# MotorDrivers.net
KiCad netlist of a schematic drawn in Altium Designer
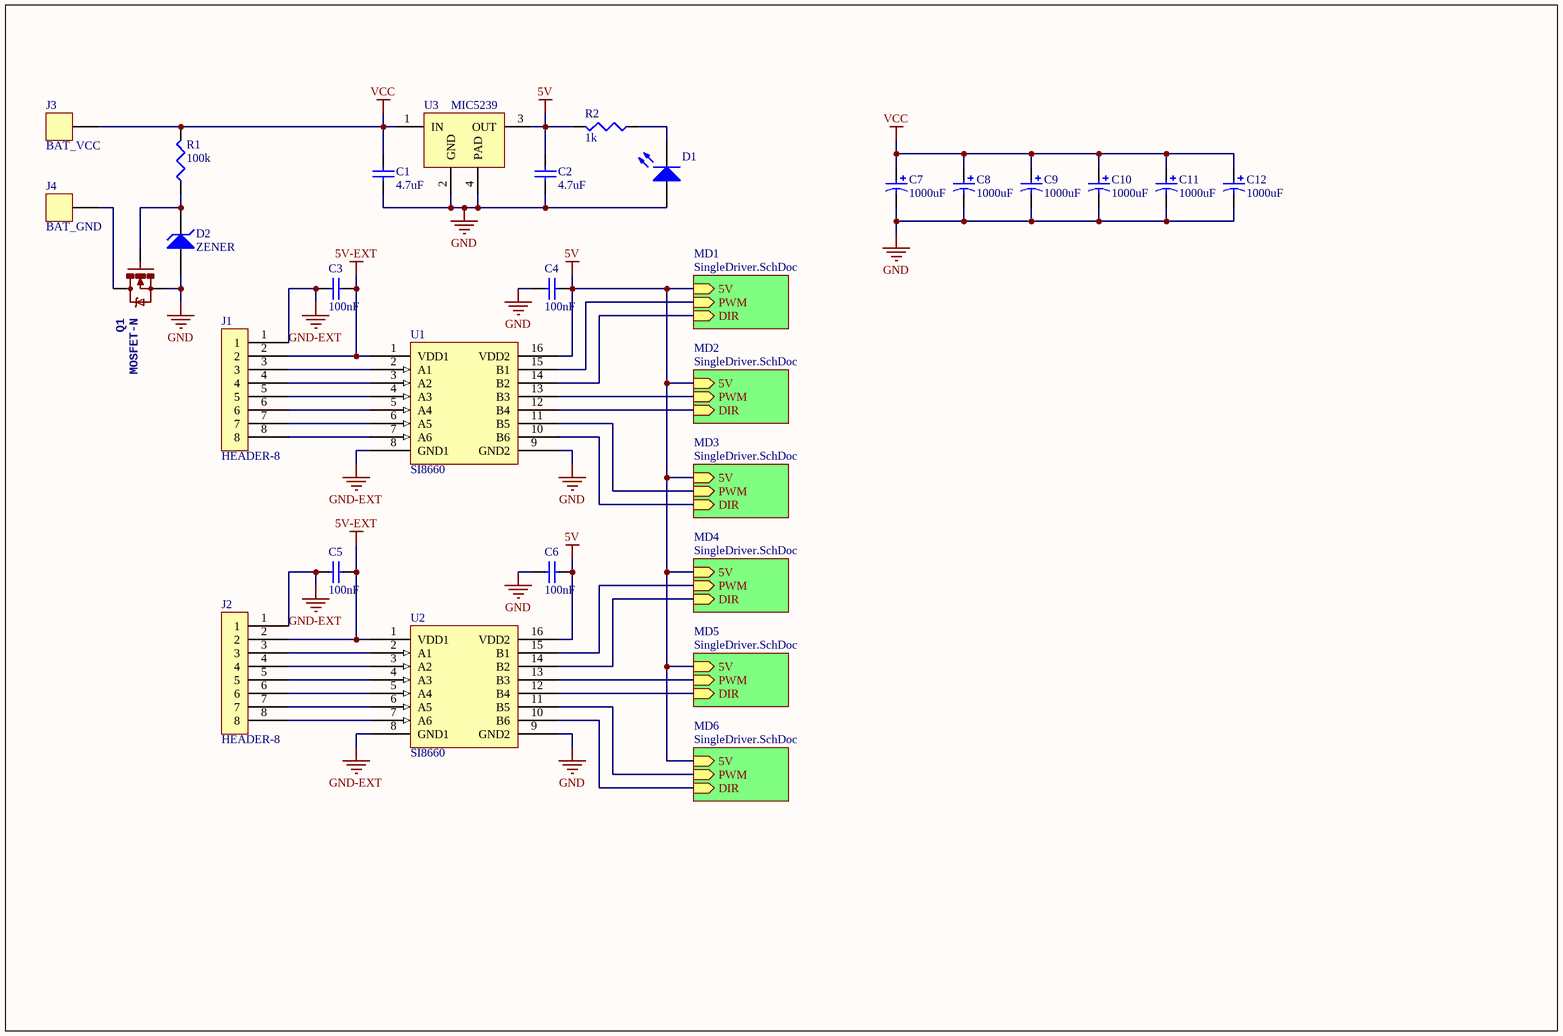
[diagram p0: MotorDrivers.SchDoc]

(export (version "E")
  (design (tool "Eeschema 10.0.6"))
  (components
    (comp (ref "C1")
      (value "4.7uF")
      (footprint "C1206")
      (description "Capacitor (Semiconductor SIM Model)")
      (fields (field (name "PUBLISHER") "Altium Limited"))
      (libsource (lib "Miscellaneous Devices") (part "Cap Semi"))
    )
    (comp (ref "C2")
      (value "4.7uF")
      (footprint "C1206")
      (description "Capacitor (Semiconductor SIM Model)")
      (fields (field (name "PUBLISHER") "Altium Limited"))
      (libsource (lib "Miscellaneous Devices") (part "Cap Semi"))
    )
    (comp (ref "C3")
      (value "100nF")
      (footprint "1608[0603]")
      (description "Capacitor (Semiconductor SIM Model)")
      (fields (field (name "PUBLISHER") "Altium Limited"))
      (libsource (lib "Miscellaneous Devices") (part "Cap Semi"))
    )
    (comp (ref "C4")
      (value "100nF")
      (footprint "1608[0603]")
      (description "Capacitor (Semiconductor SIM Model)")
      (fields (field (name "PUBLISHER") "Altium Limited"))
      (libsource (lib "Miscellaneous Devices") (part "Cap Semi"))
    )
    (comp (ref "C5")
      (value "100nF")
      (footprint "1608[0603]")
      (description "Capacitor (Semiconductor SIM Model)")
      (fields (field (name "PUBLISHER") "Altium Limited"))
      (libsource (lib "Miscellaneous Devices") (part "Cap Semi"))
    )
    (comp (ref "C6")
      (value "100nF")
      (footprint "1608[0603]")
      (description "Capacitor (Semiconductor SIM Model)")
      (fields (field (name "PUBLISHER") "Altium Limited"))
      (libsource (lib "Miscellaneous Devices") (part "Cap Semi"))
    )
    (comp (ref "C7")
      (value "1000uF")
      (footprint "cap_radial_20")
      (libsource (lib "passive") (part "cap_pol"))
    )
    (comp (ref "C8")
      (value "1000uF")
      (footprint "cap_radial_20")
      (libsource (lib "passive") (part "cap_pol"))
    )
    (comp (ref "C9")
      (value "1000uF")
      (footprint "cap_radial_20")
      (libsource (lib "passive") (part "cap_pol"))
    )
    (comp (ref "C10")
      (value "1000uF")
      (footprint "cap_radial_20")
      (libsource (lib "passive") (part "cap_pol"))
    )
    (comp (ref "C11")
      (value "1000uF")
      (footprint "cap_radial_20")
      (libsource (lib "passive") (part "cap_pol"))
    )
    (comp (ref "C12")
      (value "1000uF")
      (footprint "cap_radial_20")
      (libsource (lib "passive") (part "cap_pol"))
    )
    (comp (ref "D1")
      (value "LED2")
      (footprint "1608[0603]")
      (description "Typical RED, GREEN, YELLOW, AMBER GaAs LED")
      (fields (field (name "PUBLISHER") "Altium Limited"))
      (libsource (lib "Miscellaneous Devices") (part "LED2"))
    )
    (comp (ref "D2")
      (value "ZENER")
      (footprint "SODFL370X135-2N")
      (libsource (lib "power") (part "ZENER-DIODE"))
    )
    (comp (ref "J1")
      (value "HEADER-8")
      (footprint "MICRO-MATCH-8")
      (libsource (lib "connectors") (part "HEADER-8"))
    )
    (comp (ref "J2")
      (value "HEADER-8")
      (footprint "MICRO-MATCH-8")
      (libsource (lib "connectors") (part "HEADER-8"))
    )
    (comp (ref "J3")
      (value "BAT_VCC")
      (footprint "HIGH-POWER-VIA")
      (libsource (lib "connectors") (part "HEADER-1"))
    )
    (comp (ref "J4")
      (value "BAT_GND")
      (footprint "HIGH-POWER-VIA")
      (libsource (lib "connectors") (part "HEADER-1"))
    )
    (comp (ref "Q1") (value "MOSFET-N") (footprint "SOT669") (libsource (lib "mosfets") (part "MOSFET-N")))
    (comp (ref "R1")
      (value "100k")
      (footprint "J1-0603")
      (description "Resistor")
      (fields (field (name "PUBLISHER") "Altium Limited"))
      (libsource (lib "Miscellaneous Devices") (part "Res3"))
    )
    (comp (ref "R2")
      (value "1k")
      (footprint "J1-0603")
      (description "Resistor")
      (fields (field (name "PUBLISHER") "Altium Limited"))
      (libsource (lib "Miscellaneous Devices") (part "Res3"))
    )
    (comp (ref "U1") (value "SI8660") (footprint "SOIC16") (libsource (lib "digital") (part "SI8660")))
    (comp (ref "U2") (value "SI8660") (footprint "SOIC16") (libsource (lib "digital") (part "SI8660")))
    (comp (ref "U3")
      (value "MIC5239")
      (footprint "SOT230P700X180-4N")
      (libsource (lib "power") (part "MIC5239"))
    )
  )
  (nets
    (net (code "1") (name "/DIR") (class "Default")
      (node (ref "U2") (pin "10") (pinfunction "B6_10") (pintype "passive"))
    )
    (net (code "2") (name "/DIR_1") (class "Default")
      (node (ref "U1") (pin "14") (pinfunction "B2_14") (pintype "passive"))
    )
    (net (code "3") (name "/DIR_2") (class "Default")
      (node (ref "U1") (pin "12") (pinfunction "B4_12") (pintype "passive"))
    )
    (net (code "4") (name "/DIR_3") (class "Default")
      (node (ref "U1") (pin "10") (pinfunction "B6_10") (pintype "passive"))
    )
    (net (code "5") (name "/DIR_4") (class "Default")
      (node (ref "U2") (pin "14") (pinfunction "B2_14") (pintype "passive"))
    )
    (net (code "6") (name "/DIR_5") (class "Default")
      (node (ref "U2") (pin "12") (pinfunction "B4_12") (pintype "passive"))
    )
    (net (code "7") (name "/PWM") (class "Default")
      (node (ref "U2") (pin "11") (pinfunction "B5_11") (pintype "passive"))
    )
    (net (code "8") (name "/PWM_1") (class "Default")
      (node (ref "U1") (pin "15") (pinfunction "B1_15") (pintype "passive"))
    )
    (net (code "9") (name "/PWM_2") (class "Default")
      (node (ref "U1") (pin "13") (pinfunction "B3_13") (pintype "passive"))
    )
    (net (code "10") (name "/PWM_3") (class "Default")
      (node (ref "U1") (pin "11") (pinfunction "B5_11") (pintype "passive"))
    )
    (net (code "11") (name "/PWM_4") (class "Default")
      (node (ref "U2") (pin "15") (pinfunction "B1_15") (pintype "passive"))
    )
    (net (code "12") (name "/PWM_5") (class "Default")
      (node (ref "U2") (pin "13") (pinfunction "B3_13") (pintype "passive"))
    )
    (net (code "13") (name "5V") (class "Default")
      (node (ref "C2") (pin "2") (pinfunction "2_2") (pintype "passive"))
      (node (ref "C4") (pin "1") (pinfunction "1_1") (pintype "passive"))
      (node (ref "C6") (pin "1") (pinfunction "1_1") (pintype "passive"))
      (node (ref "R2") (pin "2") (pinfunction "2_2") (pintype "passive"))
      (node (ref "U1") (pin "16") (pinfunction "VDD2_16") (pintype "power_in"))
      (node (ref "U2") (pin "16") (pinfunction "VDD2_16") (pintype "power_in"))
      (node (ref "U3") (pin "3") (pinfunction "OUT_3") (pintype "power_in"))
    )
    (net (code "14") (name "5V-EXT") (class "Default")
      (node (ref "C3") (pin "1") (pinfunction "1_1") (pintype "passive"))
      (node (ref "C5") (pin "1") (pinfunction "1_1") (pintype "passive"))
      (node (ref "J1") (pin "2") (pinfunction "2_2") (pintype "passive"))
      (node (ref "J2") (pin "2") (pinfunction "2_2") (pintype "passive"))
      (node (ref "U1") (pin "1") (pinfunction "VDD1_1") (pintype "power_in"))
      (node (ref "U2") (pin "1") (pinfunction "VDD1_1") (pintype "power_in"))
    )
    (net (code "15") (name "GND") (class "Default")
      (node (ref "C1") (pin "1") (pinfunction "1_1") (pintype "passive"))
      (node (ref "C10") (pin "1") (pinfunction "1_1") (pintype "passive"))
      (node (ref "C11") (pin "1") (pinfunction "1_1") (pintype "passive"))
      (node (ref "C12") (pin "1") (pinfunction "1_1") (pintype "passive"))
      (node (ref "C2") (pin "1") (pinfunction "1_1") (pintype "passive"))
      (node (ref "C4") (pin "2") (pinfunction "2_2") (pintype "passive"))
      (node (ref "C6") (pin "2") (pinfunction "2_2") (pintype "passive"))
      (node (ref "C7") (pin "1") (pinfunction "1_1") (pintype "passive"))
      (node (ref "C8") (pin "1") (pinfunction "1_1") (pintype "passive"))
      (node (ref "C9") (pin "1") (pinfunction "1_1") (pintype "passive"))
      (node (ref "D1") (pin "1") (pinfunction "A_1") (pintype "passive"))
      (node (ref "D2") (pin "2") (pinfunction "2_2") (pintype "passive"))
      (node (ref "Q1") (pin "S") (pinfunction "S_S") (pintype "passive"))
      (node (ref "U1") (pin "9") (pinfunction "GND2_9") (pintype "power_in"))
      (node (ref "U2") (pin "9") (pinfunction "GND2_9") (pintype "power_in"))
      (node (ref "U3") (pin "2") (pinfunction "GND_2") (pintype "power_in"))
      (node (ref "U3") (pin "4") (pinfunction "PAD_4") (pintype "power_in"))
    )
    (net (code "16") (name "GND-EXT") (class "Default")
      (node (ref "C3") (pin "2") (pinfunction "2_2") (pintype "passive"))
      (node (ref "C5") (pin "2") (pinfunction "2_2") (pintype "passive"))
      (node (ref "J1") (pin "1") (pinfunction "1_1") (pintype "passive"))
      (node (ref "J2") (pin "1") (pinfunction "1_1") (pintype "passive"))
      (node (ref "U1") (pin "8") (pinfunction "GND1_8") (pintype "power_in"))
      (node (ref "U2") (pin "8") (pinfunction "GND1_8") (pintype "power_in"))
    )
    (net (code "17") (name "Net-(D1-K)") (class "Default")
      (node (ref "D1") (pin "2") (pinfunction "K_2") (pintype "passive"))
      (node (ref "R2") (pin "1") (pinfunction "1_1") (pintype "passive"))
    )
    (net (code "18") (name "Net-(D2-Pad1)") (class "Default")
      (node (ref "D2") (pin "1") (pinfunction "1_1") (pintype "passive"))
      (node (ref "Q1") (pin "G") (pinfunction "G_G") (pintype "passive"))
      (node (ref "R1") (pin "1") (pinfunction "1_1") (pintype "passive"))
    )
    (net (code "19") (name "Net-(J4-Pad1)") (class "Default")
      (node (ref "J4") (pin "1") (pinfunction "1_1") (pintype "passive"))
      (node (ref "Q1") (pin "D") (pinfunction "D_D") (pintype "passive"))
    )
    (net (code "20") (name "Net-(U1-A1)") (class "Default")
      (node (ref "J1") (pin "3") (pinfunction "3_3") (pintype "passive"))
      (node (ref "U1") (pin "2") (pinfunction "A1_2") (pintype "input"))
    )
    (net (code "21") (name "Net-(U1-A2)") (class "Default")
      (node (ref "J1") (pin "4") (pinfunction "4_4") (pintype "passive"))
      (node (ref "U1") (pin "3") (pinfunction "A2_3") (pintype "input"))
    )
    (net (code "22") (name "Net-(U1-A3)") (class "Default")
      (node (ref "J1") (pin "5") (pinfunction "5_5") (pintype "passive"))
      (node (ref "U1") (pin "4") (pinfunction "A3_4") (pintype "input"))
    )
    (net (code "23") (name "Net-(U1-A4)") (class "Default")
      (node (ref "J1") (pin "6") (pinfunction "6_6") (pintype "passive"))
      (node (ref "U1") (pin "5") (pinfunction "A4_5") (pintype "input"))
    )
    (net (code "24") (name "Net-(U1-A5)") (class "Default")
      (node (ref "J1") (pin "7") (pinfunction "7_7") (pintype "passive"))
      (node (ref "U1") (pin "6") (pinfunction "A5_6") (pintype "input"))
    )
    (net (code "25") (name "Net-(U1-A6)") (class "Default")
      (node (ref "J1") (pin "8") (pinfunction "8_8") (pintype "passive"))
      (node (ref "U1") (pin "7") (pinfunction "A6_7") (pintype "input"))
    )
    (net (code "26") (name "Net-(U2-A1)") (class "Default")
      (node (ref "J2") (pin "3") (pinfunction "3_3") (pintype "passive"))
      (node (ref "U2") (pin "2") (pinfunction "A1_2") (pintype "input"))
    )
    (net (code "27") (name "Net-(U2-A2)") (class "Default")
      (node (ref "J2") (pin "4") (pinfunction "4_4") (pintype "passive"))
      (node (ref "U2") (pin "3") (pinfunction "A2_3") (pintype "input"))
    )
    (net (code "28") (name "Net-(U2-A3)") (class "Default")
      (node (ref "J2") (pin "5") (pinfunction "5_5") (pintype "passive"))
      (node (ref "U2") (pin "4") (pinfunction "A3_4") (pintype "input"))
    )
    (net (code "29") (name "Net-(U2-A4)") (class "Default")
      (node (ref "J2") (pin "6") (pinfunction "6_6") (pintype "passive"))
      (node (ref "U2") (pin "5") (pinfunction "A4_5") (pintype "input"))
    )
    (net (code "30") (name "Net-(U2-A5)") (class "Default")
      (node (ref "J2") (pin "7") (pinfunction "7_7") (pintype "passive"))
      (node (ref "U2") (pin "6") (pinfunction "A5_6") (pintype "input"))
    )
    (net (code "31") (name "Net-(U2-A6)") (class "Default")
      (node (ref "J2") (pin "8") (pinfunction "8_8") (pintype "passive"))
      (node (ref "U2") (pin "7") (pinfunction "A6_7") (pintype "input"))
    )
    (net (code "32") (name "VCC") (class "Default")
      (node (ref "C1") (pin "2") (pinfunction "2_2") (pintype "passive"))
      (node (ref "C10") (pin "2") (pinfunction "2_2") (pintype "passive"))
      (node (ref "C11") (pin "2") (pinfunction "2_2") (pintype "passive"))
      (node (ref "C12") (pin "2") (pinfunction "2_2") (pintype "passive"))
      (node (ref "C7") (pin "2") (pinfunction "2_2") (pintype "passive"))
      (node (ref "C8") (pin "2") (pinfunction "2_2") (pintype "passive"))
      (node (ref "C9") (pin "2") (pinfunction "2_2") (pintype "passive"))
      (node (ref "J3") (pin "1") (pinfunction "1_1") (pintype "passive"))
      (node (ref "R1") (pin "2") (pinfunction "2_2") (pintype "passive"))
      (node (ref "U3") (pin "1") (pinfunction "IN_1") (pintype "power_in"))
    )
  )
)
